# prog_addapter.net
KiCad netlist of a schematic drawn in EAGLE
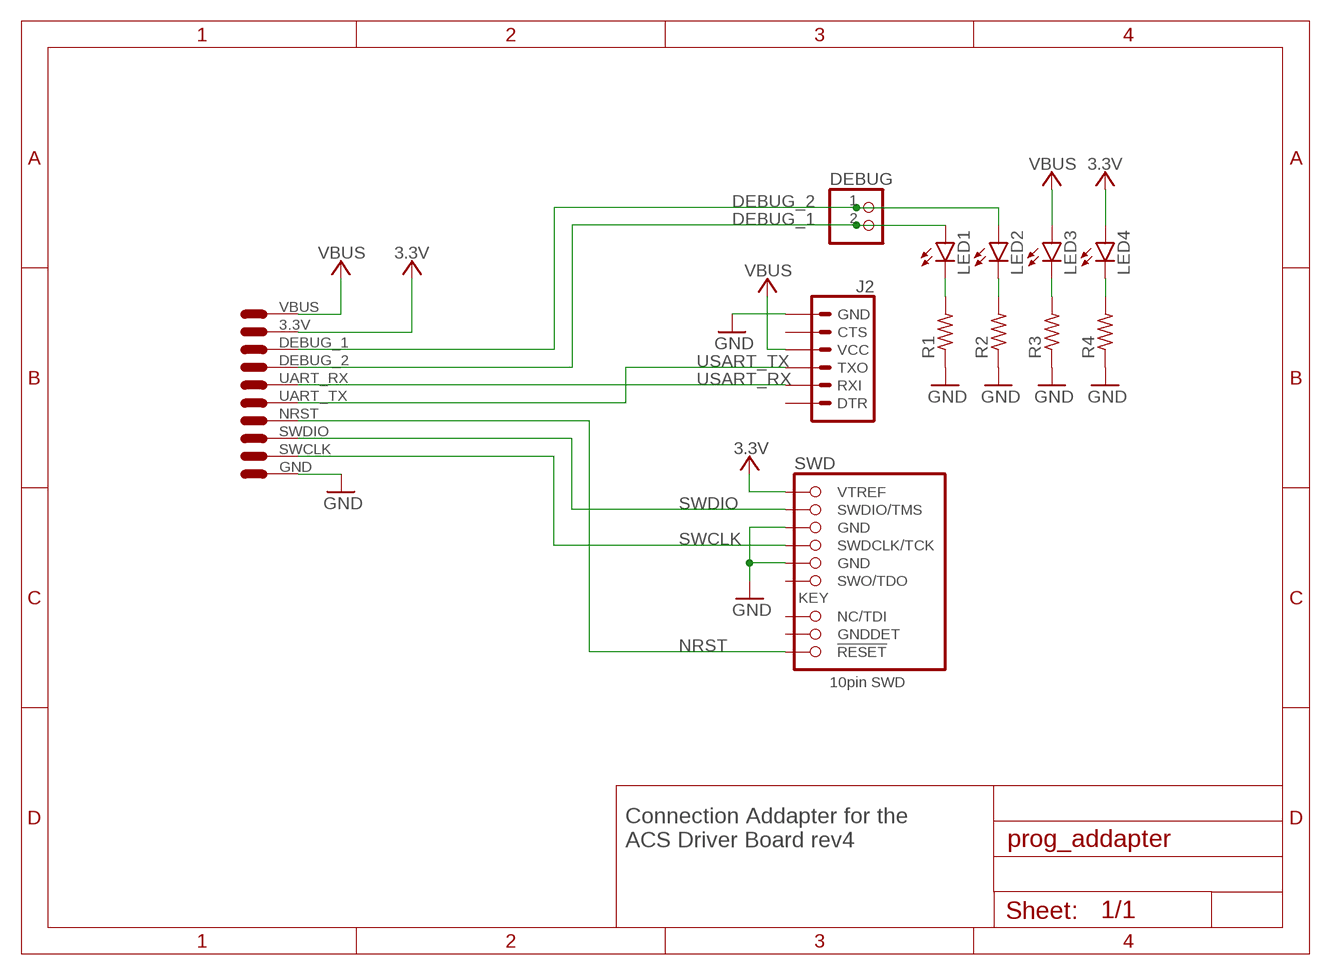
[diagram p0: schematic, sheet 1]

(export (version "E")
  (design (tool "Eeschema 10.0.6"))
  (components
    (comp (ref "DEBUG")
      (value "PINHD-1X2")
      (footprint "eagle-import:1X02")
      (libsource (lib "eagle-import") (part "PINHD-1X2"))
    )
    (comp (ref "J2")
      (value "6_PIN_SERIAL_TARGETSILK")
      (footprint "eagle-import:6_PIN_SERIAL_TARGET_SIDE_W_SILK")
      (libsource (lib "eagle-import") (part "6_PIN_SERIAL_TARGETSILK"))
    )
    (comp (ref "LED1")
      (value "LEDCHIPLED_0603")
      (footprint "eagle-import:CHIPLED_0603")
      (libsource (lib "eagle-import") (part "LEDCHIPLED_0603"))
    )
    (comp (ref "LED2")
      (value "LEDCHIPLED_0603")
      (footprint "eagle-import:CHIPLED_0603")
      (libsource (lib "eagle-import") (part "LEDCHIPLED_0603"))
    )
    (comp (ref "LED3")
      (value "LEDCHIPLED_0603")
      (footprint "eagle-import:CHIPLED_0603")
      (libsource (lib "eagle-import") (part "LEDCHIPLED_0603"))
    )
    (comp (ref "LED4")
      (value "LEDCHIPLED_0603")
      (footprint "eagle-import:CHIPLED_0603")
      (libsource (lib "eagle-import") (part "LEDCHIPLED_0603"))
    )
    (comp (ref "R1")
      (value "R-US_0402-B-NOSILK")
      (footprint "eagle-import:.0402-B-NOSILK")
      (libsource (lib "eagle-import") (part "R-US_0402-B-NOSILK"))
    )
    (comp (ref "R2")
      (value "R-US_0402-B-NOSILK")
      (footprint "eagle-import:.0402-B-NOSILK")
      (libsource (lib "eagle-import") (part "R-US_0402-B-NOSILK"))
    )
    (comp (ref "R3")
      (value "R-US_0402-B-NOSILK")
      (footprint "eagle-import:.0402-B-NOSILK")
      (libsource (lib "eagle-import") (part "R-US_0402-B-NOSILK"))
    )
    (comp (ref "R4")
      (value "R-US_0402-B-NOSILK")
      (footprint "eagle-import:.0402-B-NOSILK")
      (libsource (lib "eagle-import") (part "R-US_0402-B-NOSILK"))
    )
    (comp (ref "SWD")
      (value "1.27MM-SWD-CONNECTOR")
      (footprint "eagle-import:1.27MM_2X5")
      (libsource (lib "eagle-import") (part "1.27MM-SWD-CONNECTOR"))
    )
    (comp (ref "U$1")
      (value "DEBUG_CON")
      (footprint "eagle-import:DEBUG_CON")
      (libsource (lib "eagle-import") (part "DEBUG_CON"))
    )
  )
  (nets
    (net (code "1") (name "/DEBUG_1") (class "Default")
      (node (ref "DEBUG") (pin "1") (pinfunction "1_1") (pintype "passive"))
      (node (ref "LED2") (pin "A") (pinfunction "A_A") (pintype "passive"))
      (node (ref "U$1") (pin "DEBUG_1") (pinfunction "3_DEBUG_1") (pintype "bidirectional"))
    )
    (net (code "2") (name "/DEBUG_2") (class "Default")
      (node (ref "DEBUG") (pin "2") (pinfunction "2_2") (pintype "passive"))
      (node (ref "LED1") (pin "A") (pinfunction "A_A") (pintype "passive"))
      (node (ref "U$1") (pin "DEBUG_2") (pinfunction "4_DEBUG_2") (pintype "bidirectional"))
    )
    (net (code "3") (name "/NRST") (class "Default")
      (node (ref "SWD") (pin "!RESET") (pinfunction "~{RESET}_!RESET") (pintype "passive"))
      (node (ref "U$1") (pin "NRST") (pinfunction "7_NRST") (pintype "bidirectional"))
    )
    (net (code "4") (name "/SWCLK") (class "Default")
      (node (ref "SWD") (pin "SWDCLK") (pinfunction "SWDCLK/TCK_SWDCLK") (pintype "passive"))
      (node (ref "U$1") (pin "SWCLK") (pinfunction "9_SWCLK") (pintype "bidirectional"))
    )
    (net (code "5") (name "/SWDIO") (class "Default")
      (node (ref "SWD") (pin "SWDIO") (pinfunction "SWDIO/TMS_SWDIO") (pintype "passive"))
      (node (ref "U$1") (pin "SWDIO") (pinfunction "8_SWDIO") (pintype "bidirectional"))
    )
    (net (code "6") (name "/USART_RX") (class "Default")
      (node (ref "J2") (pin "P$3") (pinfunction "RXI_P$3") (pintype "passive"))
      (node (ref "U$1") (pin "UART_RX") (pinfunction "5_UART_RX") (pintype "bidirectional"))
    )
    (net (code "7") (name "/USART_TX") (class "Default")
      (node (ref "J2") (pin "P$2") (pinfunction "TXO_P$2") (pintype "passive"))
      (node (ref "U$1") (pin "UART_TX") (pinfunction "6_UART_TX") (pintype "bidirectional"))
    )
    (net (code "8") (name "3.3V") (class "Default")
      (node (ref "LED4") (pin "A") (pinfunction "A_A") (pintype "passive"))
      (node (ref "SWD") (pin "VTREF") (pinfunction "VTREF_VTREF") (pintype "passive"))
      (node (ref "U$1") (pin "3.3V") (pinfunction "2_3.3V") (pintype "bidirectional"))
    )
    (net (code "9") (name "GND") (class "Default")
      (node (ref "J2") (pin "P$6") (pinfunction "GND_P$6") (pintype "passive"))
      (node (ref "R1") (pin "1") (pinfunction "1_1") (pintype "passive"))
      (node (ref "R2") (pin "1") (pinfunction "1_1") (pintype "passive"))
      (node (ref "R3") (pin "1") (pinfunction "1_1") (pintype "passive"))
      (node (ref "R4") (pin "1") (pinfunction "1_1") (pintype "passive"))
      (node (ref "SWD") (pin "GND") (pinfunction "GND_GND") (pintype "passive"))
      (node (ref "SWD") (pin "GND@2") (pinfunction "GND_GND@2") (pintype "passive"))
      (node (ref "U$1") (pin "GND") (pinfunction "10_GND") (pintype "bidirectional"))
    )
    (net (code "10") (name "Net-(LED1-PadC)") (class "Default")
      (node (ref "LED1") (pin "C") (pinfunction "C_C") (pintype "passive"))
      (node (ref "R1") (pin "2") (pinfunction "2_2") (pintype "passive"))
    )
    (net (code "11") (name "Net-(LED2-PadC)") (class "Default")
      (node (ref "LED2") (pin "C") (pinfunction "C_C") (pintype "passive"))
      (node (ref "R2") (pin "2") (pinfunction "2_2") (pintype "passive"))
    )
    (net (code "12") (name "Net-(LED3-PadC)") (class "Default")
      (node (ref "LED3") (pin "C") (pinfunction "C_C") (pintype "passive"))
      (node (ref "R3") (pin "2") (pinfunction "2_2") (pintype "passive"))
    )
    (net (code "13") (name "Net-(LED4-PadC)") (class "Default")
      (node (ref "LED4") (pin "C") (pinfunction "C_C") (pintype "passive"))
      (node (ref "R4") (pin "2") (pinfunction "2_2") (pintype "passive"))
    )
    (net (code "14") (name "VBUS") (class "Default")
      (node (ref "J2") (pin "P$4") (pinfunction "VCC_P$4") (pintype "passive"))
      (node (ref "LED3") (pin "A") (pinfunction "A_A") (pintype "passive"))
      (node (ref "U$1") (pin "VBUS") (pinfunction "1_VBUS") (pintype "bidirectional"))
    )
    (net (code "15") (name "unconnected-(J2-CTS-PadP$5)") (class "Default")
      (node (ref "J2") (pin "P$5") (pinfunction "CTS_P$5") (pintype "passive"))
    )
    (net (code "16") (name "unconnected-(J2-DTR-PadP$1)") (class "Default")
      (node (ref "J2") (pin "P$1") (pinfunction "DTR_P$1") (pintype "passive"))
    )
    (net (code "17") (name "unconnected-(SWD-NC{slash}TDI-PadNC)") (class "Default")
      (node (ref "SWD") (pin "NC") (pinfunction "NC/TDI_NC") (pintype "passive"))
    )
    (net (code "18") (name "unconnected-(SWD-PadGNDDET)") (class "Default")
      (node (ref "SWD") (pin "GNDDET") (pinfunction "GNDDET_GNDDET") (pintype "passive"))
    )
    (net (code "19") (name "unconnected-(SWD-SWO{slash}TDO-PadSWO)") (class "Default")
      (node (ref "SWD") (pin "SWO") (pinfunction "SWO/TDO_SWO") (pintype "passive"))
    )
  )
)
